# Current_Driver_1.net
KiCad netlist of a schematic drawn in Altium Designer
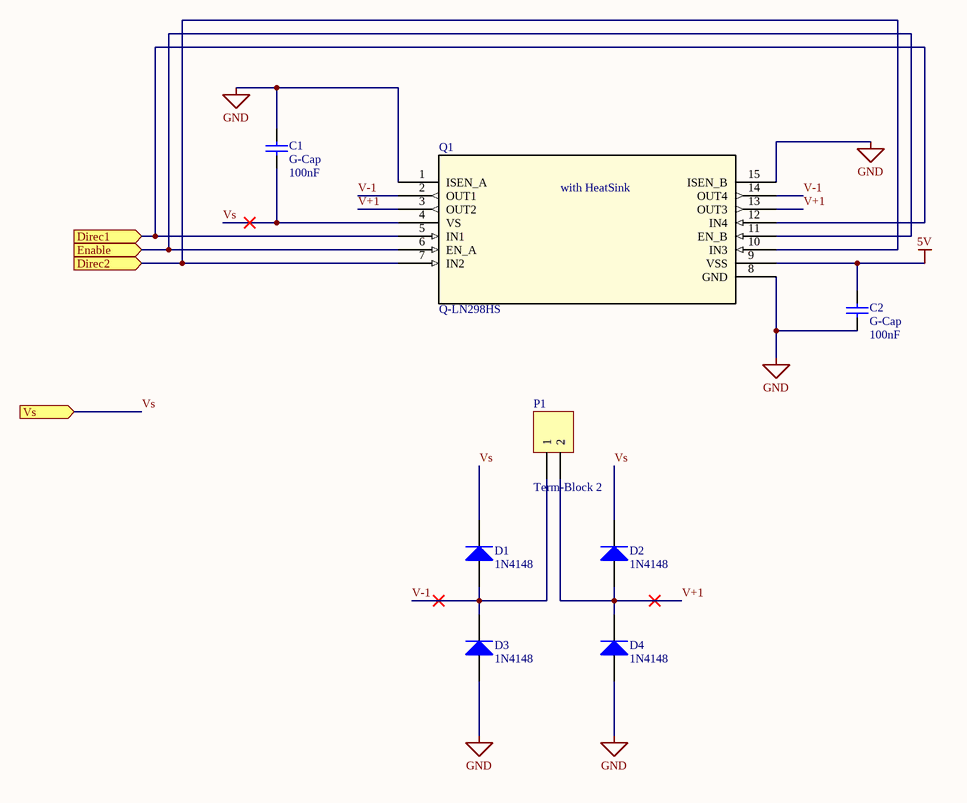
[diagram p0: Current_Driver_1.SchDoc]

(export (version "E")
  (design (tool "Eeschema 10.0.6"))
  (components
    (comp (ref "C1")
      (value "G-Cap")
      (footprint "Cap2.54mm_LGE1.0")
      (description "Capacitor (specify value)")
      (fields (field (name "ALTIUM_VALUE") "100nF") (field (name "PUBLISHER") "Altium Limited"))
      (libsource (lib "PartsDatabaseV16.1") (part "G-Cap"))
    )
    (comp (ref "C2")
      (value "G-Cap")
      (footprint "Cap2.54mm_LGE1.0")
      (description "Capacitor (specify value)")
      (fields (field (name "ALTIUM_VALUE") "100nF") (field (name "PUBLISHER") "Altium Limited"))
      (libsource (lib "PartsDatabaseV16.1") (part "G-Cap"))
    )
    (comp (ref "D1")
      (value "1N4148")
      (footprint "DO-41_XLGE1.2")
      (description "High-speed Diode")
      (libsource (lib "PartsDatabaseV16.1") (part "T-DiodeRect"))
    )
    (comp (ref "D2")
      (value "1N4148")
      (footprint "DO-41_XLGE1.2")
      (description "High-speed Diode")
      (libsource (lib "PartsDatabaseV16.1") (part "T-DiodeRect"))
    )
    (comp (ref "D3")
      (value "1N4148")
      (footprint "DO-41_XLGE1.2")
      (description "High-speed Diode")
      (libsource (lib "PartsDatabaseV16.1") (part "T-DiodeRect"))
    )
    (comp (ref "D4")
      (value "1N4148")
      (footprint "DO-41_XLGE1.2")
      (description "High-speed Diode")
      (libsource (lib "PartsDatabaseV16.1") (part "T-DiodeRect"))
    )
    (comp (ref "P1")
      (value "Term-Block 2")
      (footprint "TERM-BLOCK-5.08MM-2POS")
      (description "Terminal-Block 1x2")
      (fields (field (name "PUBLISHER") "Altium Limited"))
      (libsource (lib "PartsDatabaseV16.1") (part "C-Block2"))
    )
    (comp (ref "Q1")
      (value "Q-LN298HS")
      (footprint "Multiwatt15_V_ELEC391HS")
      (description "LN298 - IC Bridge Driver Par 15Multiwatt")
      (fields
        (field (name "MANUFACTURER_PART_NUMBER") "L298N")
        (field (name "COPYRIGHT") "Copyright (C) 2015 Accelerated Designs. All rights reserved")
      )
      (libsource (lib "Additional Parts 391") (part "Q-LN298HS"))
    )
  )
  (nets
    (net (code "1") (name "/Direc1") (class "Default")
      (node (ref "Q1") (pin "12") (pinfunction "IN4_12") (pintype "input"))
      (node (ref "Q1") (pin "5") (pinfunction "IN1_5") (pintype "input"))
    )
    (net (code "2") (name "/Direc2") (class "Default")
      (node (ref "Q1") (pin "10") (pinfunction "IN3_10") (pintype "input"))
      (node (ref "Q1") (pin "7") (pinfunction "IN2_7") (pintype "input"))
    )
    (net (code "3") (name "/Enable") (class "Default")
      (node (ref "Q1") (pin "11") (pinfunction "EN_B_11") (pintype "input"))
      (node (ref "Q1") (pin "6") (pinfunction "EN_A_6") (pintype "input"))
    )
    (net (code "4") (name "/V+1") (class "Default")
      (node (ref "D2") (pin "1") (pinfunction "A_1") (pintype "passive"))
      (node (ref "D4") (pin "2") (pinfunction "K_2") (pintype "passive"))
      (node (ref "P1") (pin "2") (pinfunction "2_2") (pintype "passive"))
      (node (ref "Q1") (pin "13") (pinfunction "OUT3_13") (pintype "output"))
      (node (ref "Q1") (pin "3") (pinfunction "OUT2_3") (pintype "output"))
    )
    (net (code "5") (name "/V-1") (class "Default")
      (node (ref "D1") (pin "1") (pinfunction "A_1") (pintype "passive"))
      (node (ref "D3") (pin "2") (pinfunction "K_2") (pintype "passive"))
      (node (ref "P1") (pin "1") (pinfunction "1_1") (pintype "passive"))
      (node (ref "Q1") (pin "14") (pinfunction "OUT4_14") (pintype "output"))
      (node (ref "Q1") (pin "2") (pinfunction "OUT1_2") (pintype "output"))
    )
    (net (code "6") (name "/Vs") (class "Default")
      (node (ref "C1") (pin "1") (pinfunction "1_1") (pintype "passive"))
      (node (ref "D1") (pin "2") (pinfunction "K_2") (pintype "passive"))
      (node (ref "D2") (pin "2") (pinfunction "K_2") (pintype "passive"))
      (node (ref "Q1") (pin "4") (pinfunction "VS_4") (pintype "power_in"))
    )
    (net (code "7") (name "5V") (class "Default")
      (node (ref "C2") (pin "2") (pinfunction "2_2") (pintype "passive"))
      (node (ref "Q1") (pin "9") (pinfunction "VSS_9") (pintype "power_in"))
    )
    (net (code "8") (name "GND") (class "Default")
      (node (ref "C1") (pin "2") (pinfunction "2_2") (pintype "passive"))
      (node (ref "C2") (pin "1") (pinfunction "1_1") (pintype "passive"))
      (node (ref "D3") (pin "1") (pinfunction "A_1") (pintype "passive"))
      (node (ref "D4") (pin "1") (pinfunction "A_1") (pintype "passive"))
      (node (ref "Q1") (pin "1") (pinfunction "ISEN_A_1") (pintype "passive"))
      (node (ref "Q1") (pin "15") (pinfunction "ISEN_B_15") (pintype "passive"))
      (node (ref "Q1") (pin "8") (pinfunction "GND_8") (pintype "power_in"))
    )
  )
)
